# PowerBricksBoard1_X14.net
KiCad netlist of a schematic drawn in EAGLE
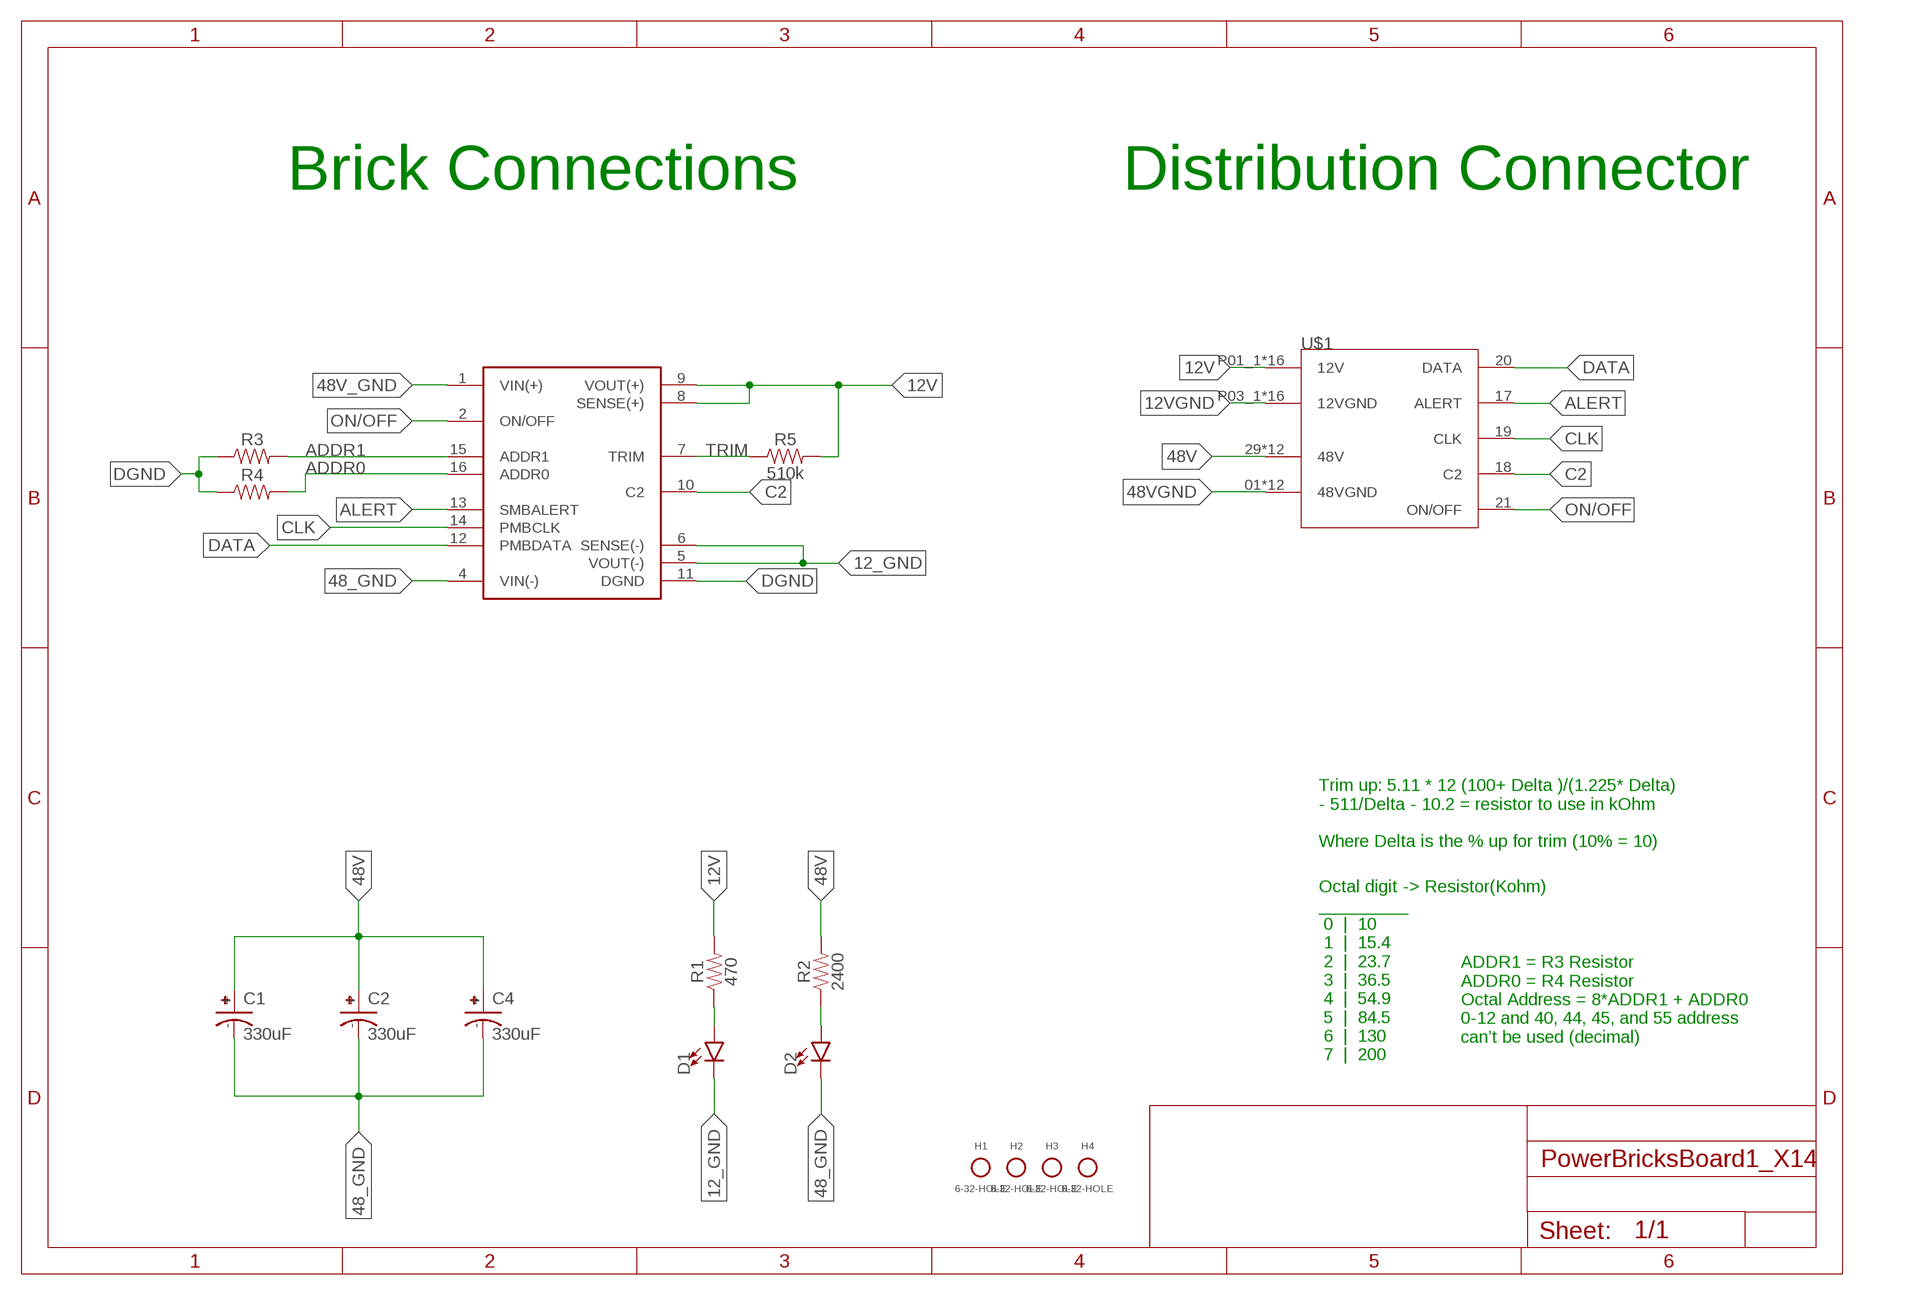
[diagram p0: schematic, sheet 1]

(export (version "E")
  (design (tool "Eeschema 10.0.6"))
  (components
    (comp (ref "C1")
      (value "330uF")
      (footprint "eagle-import:CAPAE1030X1050N")
      (fields
        (field (name "ARROW_PART_NUMBER") "UCM1H331MNL1GS")
        (field (name "MOUSER_PART_NUMBER") "647-UCM1H331MNL1GS")
      )
      (libsource (lib "eagle-import") (part "UCM1H331MNL1GS"))
    )
    (comp (ref "C2")
      (value "330uF")
      (footprint "eagle-import:CAPAE1030X1050N")
      (fields
        (field (name "ARROW_PART_NUMBER") "UCM1H331MNL1GS")
        (field (name "MOUSER_PART_NUMBER") "647-UCM1H331MNL1GS")
      )
      (libsource (lib "eagle-import") (part "UCM1H331MNL1GS"))
    )
    (comp (ref "C4")
      (value "330uF")
      (footprint "eagle-import:CAPAE1030X1050N")
      (fields
        (field (name "ARROW_PART_NUMBER") "UCM1H331MNL1GS")
        (field (name "MOUSER_PART_NUMBER") "647-UCM1H331MNL1GS")
      )
      (libsource (lib "eagle-import") (part "UCM1H331MNL1GS"))
    )
    (comp (ref "D1")
      (value "LED0603")
      (footprint "eagle-import:LED-0603")
      (libsource (lib "eagle-import") (part "LED0603"))
    )
    (comp (ref "D2")
      (value "LED0603")
      (footprint "eagle-import:LED-0603")
      (libsource (lib "eagle-import") (part "LED0603"))
    )
    (comp (ref "H1")
      (value "6-32-HOLE")
      (footprint "eagle-import:6-32-HOLE")
      (libsource (lib "eagle-import") (part "6-32-HOLE"))
    )
    (comp (ref "H2")
      (value "6-32-HOLE")
      (footprint "eagle-import:6-32-HOLE")
      (libsource (lib "eagle-import") (part "6-32-HOLE"))
    )
    (comp (ref "H3")
      (value "6-32-HOLE")
      (footprint "eagle-import:6-32-HOLE")
      (libsource (lib "eagle-import") (part "6-32-HOLE"))
    )
    (comp (ref "H4")
      (value "6-32-HOLE")
      (footprint "eagle-import:6-32-HOLE")
      (libsource (lib "eagle-import") (part "6-32-HOLE"))
    )
    (comp (ref "R1")
      (value "470")
      (footprint "eagle-import:0603")
      (libsource (lib "eagle-import") (part "RESISTOR0603"))
    )
    (comp (ref "R2")
      (value "2400")
      (footprint "eagle-import:0603")
      (libsource (lib "eagle-import") (part "RESISTOR0603"))
    )
    (comp (ref "R3")
      (value "RESISTOR0603")
      (footprint "eagle-import:0603")
      (libsource (lib "eagle-import") (part "RESISTOR0603"))
    )
    (comp (ref "R4")
      (value "RESISTOR0603")
      (footprint "eagle-import:0603")
      (libsource (lib "eagle-import") (part "RESISTOR0603"))
    )
    (comp (ref "R5")
      (value "510k")
      (footprint "eagle-import:0603")
      (libsource (lib "eagle-import") (part "RESISTOR0603"))
    )
    (comp (ref "U$1")
      (value "PETC-02-40-01-X-VT(BTOD)")
      (footprint "eagle-import:SAMTEC_PETC-02-40-01-X-VT_BTOD")
      (libsource (lib "eagle-import") (part "PETC-02-40-01-X-VT(BTOD)"))
    )
    (comp (ref "U$2")
      (value "Q48SC12050NRDH")
      (footprint "eagle-import:Q48SC12050NRDH")
      (libsource (lib "eagle-import") (part "Q48SC12050NRDH"))
    )
  )
  (nets
    (net (code "1") (name "/ADDR0") (class "Default")
      (node (ref "R4") (pin "2") (pinfunction "2_2") (pintype "passive"))
      (node (ref "U$2") (pin "16") (pinfunction "ADDR0_16") (pintype "bidirectional"))
    )
    (net (code "2") (name "/ADDR1") (class "Default")
      (node (ref "R3") (pin "2") (pinfunction "2_2") (pintype "passive"))
      (node (ref "U$2") (pin "15") (pinfunction "ADDR1_15") (pintype "bidirectional"))
    )
    (net (code "3") (name "/TRIM") (class "Default")
      (node (ref "R5") (pin "1") (pinfunction "1_1") (pintype "passive"))
      (node (ref "U$2") (pin "7") (pinfunction "TRIM_7") (pintype "bidirectional"))
    )
    (net (code "4") (name "12V") (class "Default")
      (node (ref "R1") (pin "2") (pinfunction "2_2") (pintype "passive"))
      (node (ref "R5") (pin "2") (pinfunction "2_2") (pintype "passive"))
      (node (ref "U$1") (pin "P01_1") (pinfunction "12V_P01_1") (pintype "bidirectional"))
      (node (ref "U$1") (pin "P01_2") (pinfunction "12V_P01_2") (pintype "bidirectional"))
      (node (ref "U$1") (pin "P01_3") (pinfunction "12V_P01_3") (pintype "bidirectional"))
      (node (ref "U$1") (pin "P01_4") (pinfunction "12V_P01_4") (pintype "bidirectional"))
      (node (ref "U$1") (pin "P01_5") (pinfunction "12V_P01_5") (pintype "bidirectional"))
      (node (ref "U$1") (pin "P01_6") (pinfunction "12V_P01_6") (pintype "bidirectional"))
      (node (ref "U$1") (pin "P01_7") (pinfunction "12V_P01_7") (pintype "bidirectional"))
      (node (ref "U$1") (pin "P01_8") (pinfunction "12V_P01_8") (pintype "bidirectional"))
      (node (ref "U$1") (pin "P02_1") (pinfunction "12V_P02_1") (pintype "bidirectional"))
      (node (ref "U$1") (pin "P02_2") (pinfunction "12V_P02_2") (pintype "bidirectional"))
      (node (ref "U$1") (pin "P02_3") (pinfunction "12V_P02_3") (pintype "bidirectional"))
      (node (ref "U$1") (pin "P02_4") (pinfunction "12V_P02_4") (pintype "bidirectional"))
      (node (ref "U$1") (pin "P02_5") (pinfunction "12V_P02_5") (pintype "bidirectional"))
      (node (ref "U$1") (pin "P02_6") (pinfunction "12V_P02_6") (pintype "bidirectional"))
      (node (ref "U$1") (pin "P02_7") (pinfunction "12V_P02_7") (pintype "bidirectional"))
      (node (ref "U$1") (pin "P02_8") (pinfunction "12V_P02_8") (pintype "bidirectional"))
      (node (ref "U$2") (pin "8") (pinfunction "SENSE(+)_8") (pintype "bidirectional"))
      (node (ref "U$2") (pin "9") (pinfunction "VOUT(+)_9") (pintype "bidirectional"))
    )
    (net (code "5") (name "12VGND") (class "Default")
      (node (ref "U$1") (pin "P03_1") (pinfunction "12VGND_P03_1") (pintype "bidirectional"))
      (node (ref "U$1") (pin "P03_2") (pinfunction "12VGND_P03_2") (pintype "bidirectional"))
      (node (ref "U$1") (pin "P03_3") (pinfunction "12VGND_P03_3") (pintype "bidirectional"))
      (node (ref "U$1") (pin "P03_4") (pinfunction "12VGND_P03_4") (pintype "bidirectional"))
      (node (ref "U$1") (pin "P03_5") (pinfunction "12VGND_P03_5") (pintype "bidirectional"))
      (node (ref "U$1") (pin "P03_6") (pinfunction "12VGND_P03_6") (pintype "bidirectional"))
      (node (ref "U$1") (pin "P03_7") (pinfunction "12VGND_P03_7") (pintype "bidirectional"))
      (node (ref "U$1") (pin "P03_8") (pinfunction "12VGND_P03_8") (pintype "bidirectional"))
      (node (ref "U$1") (pin "P04_1") (pinfunction "12VGND_P04_1") (pintype "bidirectional"))
      (node (ref "U$1") (pin "P04_2") (pinfunction "12VGND_P04_2") (pintype "bidirectional"))
      (node (ref "U$1") (pin "P04_3") (pinfunction "12VGND_P04_3") (pintype "bidirectional"))
      (node (ref "U$1") (pin "P04_4") (pinfunction "12VGND_P04_4") (pintype "bidirectional"))
      (node (ref "U$1") (pin "P04_5") (pinfunction "12VGND_P04_5") (pintype "bidirectional"))
      (node (ref "U$1") (pin "P04_6") (pinfunction "12VGND_P04_6") (pintype "bidirectional"))
      (node (ref "U$1") (pin "P04_7") (pinfunction "12VGND_P04_7") (pintype "bidirectional"))
      (node (ref "U$1") (pin "P04_8") (pinfunction "12VGND_P04_8") (pintype "bidirectional"))
    )
    (net (code "6") (name "12_GND") (class "Default")
      (node (ref "D1") (pin "C") (pinfunction "C_C") (pintype "passive"))
      (node (ref "U$2") (pin "5") (pinfunction "VOUT(-)_5") (pintype "bidirectional"))
      (node (ref "U$2") (pin "6") (pinfunction "SENSE(-)_6") (pintype "bidirectional"))
    )
    (net (code "7") (name "48V") (class "Default")
      (node (ref "C1") (pin "+") (pinfunction "+_+") (pintype "bidirectional"))
      (node (ref "C2") (pin "+") (pinfunction "+_+") (pintype "bidirectional"))
      (node (ref "C4") (pin "+") (pinfunction "+_+") (pintype "bidirectional"))
      (node (ref "R2") (pin "2") (pinfunction "2_2") (pintype "passive"))
      (node (ref "U$1") (pin "29") (pinfunction "48V_29") (pintype "bidirectional"))
      (node (ref "U$1") (pin "30") (pinfunction "48V_30") (pintype "bidirectional"))
      (node (ref "U$1") (pin "31") (pinfunction "48V_31") (pintype "bidirectional"))
      (node (ref "U$1") (pin "32") (pinfunction "48V_32") (pintype "bidirectional"))
      (node (ref "U$1") (pin "33") (pinfunction "48V_33") (pintype "bidirectional"))
      (node (ref "U$1") (pin "34") (pinfunction "48V_34") (pintype "bidirectional"))
      (node (ref "U$1") (pin "35") (pinfunction "48V_35") (pintype "bidirectional"))
      (node (ref "U$1") (pin "36") (pinfunction "48V_36") (pintype "bidirectional"))
      (node (ref "U$1") (pin "37") (pinfunction "48V_37") (pintype "bidirectional"))
      (node (ref "U$1") (pin "38") (pinfunction "48V_38") (pintype "bidirectional"))
      (node (ref "U$1") (pin "39") (pinfunction "48V_39") (pintype "bidirectional"))
      (node (ref "U$1") (pin "40") (pinfunction "48V_40") (pintype "bidirectional"))
    )
    (net (code "8") (name "48VGND") (class "Default")
      (node (ref "U$1") (pin "01") (pinfunction "48VGND_01") (pintype "bidirectional"))
      (node (ref "U$1") (pin "02") (pinfunction "48VGND_02") (pintype "bidirectional"))
      (node (ref "U$1") (pin "03") (pinfunction "48VGND_03") (pintype "bidirectional"))
      (node (ref "U$1") (pin "04") (pinfunction "48VGND_04") (pintype "bidirectional"))
      (node (ref "U$1") (pin "05") (pinfunction "48VGND_05") (pintype "bidirectional"))
      (node (ref "U$1") (pin "06") (pinfunction "48VGND_06") (pintype "bidirectional"))
      (node (ref "U$1") (pin "07") (pinfunction "48VGND_07") (pintype "bidirectional"))
      (node (ref "U$1") (pin "08") (pinfunction "48VGND_08") (pintype "bidirectional"))
      (node (ref "U$1") (pin "09") (pinfunction "48VGND_09") (pintype "bidirectional"))
      (node (ref "U$1") (pin "10") (pinfunction "48VGND_10") (pintype "bidirectional"))
      (node (ref "U$1") (pin "11") (pinfunction "48VGND_11") (pintype "bidirectional"))
      (node (ref "U$1") (pin "12") (pinfunction "48VGND_12") (pintype "bidirectional"))
    )
    (net (code "9") (name "48V_GND") (class "Default")
      (node (ref "U$2") (pin "1") (pinfunction "VIN(+)_1") (pintype "bidirectional"))
    )
    (net (code "10") (name "48_GND") (class "Default")
      (node (ref "C1") (pin "-") (pinfunction "-_-") (pintype "bidirectional"))
      (node (ref "C2") (pin "-") (pinfunction "-_-") (pintype "bidirectional"))
      (node (ref "C4") (pin "-") (pinfunction "-_-") (pintype "bidirectional"))
      (node (ref "D2") (pin "C") (pinfunction "C_C") (pintype "passive"))
      (node (ref "U$2") (pin "4") (pinfunction "VIN(-)_4") (pintype "bidirectional"))
    )
    (net (code "11") (name "ALERT") (class "Default")
      (node (ref "U$1") (pin "17") (pinfunction "ALERT_17") (pintype "bidirectional"))
      (node (ref "U$2") (pin "13") (pinfunction "SMBALERT_13") (pintype "bidirectional"))
    )
    (net (code "12") (name "C2") (class "Default")
      (node (ref "U$1") (pin "18") (pinfunction "C2_18") (pintype "bidirectional"))
      (node (ref "U$2") (pin "10") (pinfunction "C2_10") (pintype "bidirectional"))
    )
    (net (code "13") (name "CLK") (class "Default")
      (node (ref "U$1") (pin "19") (pinfunction "CLK_19") (pintype "bidirectional"))
      (node (ref "U$2") (pin "14") (pinfunction "PMBCLK_14") (pintype "bidirectional"))
    )
    (net (code "14") (name "DATA") (class "Default")
      (node (ref "U$1") (pin "20") (pinfunction "DATA_20") (pintype "bidirectional"))
      (node (ref "U$2") (pin "12") (pinfunction "PMBDATA_12") (pintype "bidirectional"))
    )
    (net (code "15") (name "DGND") (class "Default")
      (node (ref "R3") (pin "1") (pinfunction "1_1") (pintype "passive"))
      (node (ref "R4") (pin "1") (pinfunction "1_1") (pintype "passive"))
      (node (ref "U$2") (pin "11") (pinfunction "DGND_11") (pintype "bidirectional"))
    )
    (net (code "16") (name "Net-(D1-PadA)") (class "Default")
      (node (ref "D1") (pin "A") (pinfunction "A_A") (pintype "passive"))
      (node (ref "R1") (pin "1") (pinfunction "1_1") (pintype "passive"))
    )
    (net (code "17") (name "Net-(D2-PadA)") (class "Default")
      (node (ref "D2") (pin "A") (pinfunction "A_A") (pintype "passive"))
      (node (ref "R2") (pin "1") (pinfunction "1_1") (pintype "passive"))
    )
    (net (code "18") (name "ON{slash}OFF") (class "Default")
      (node (ref "U$1") (pin "21") (pinfunction "ON/OFF_21") (pintype "bidirectional"))
      (node (ref "U$2") (pin "2") (pinfunction "ON/OFF_2") (pintype "bidirectional"))
    )
  )
)
